# ESP32_S2.net
KiCad netlist of a schematic drawn in Altium Designer
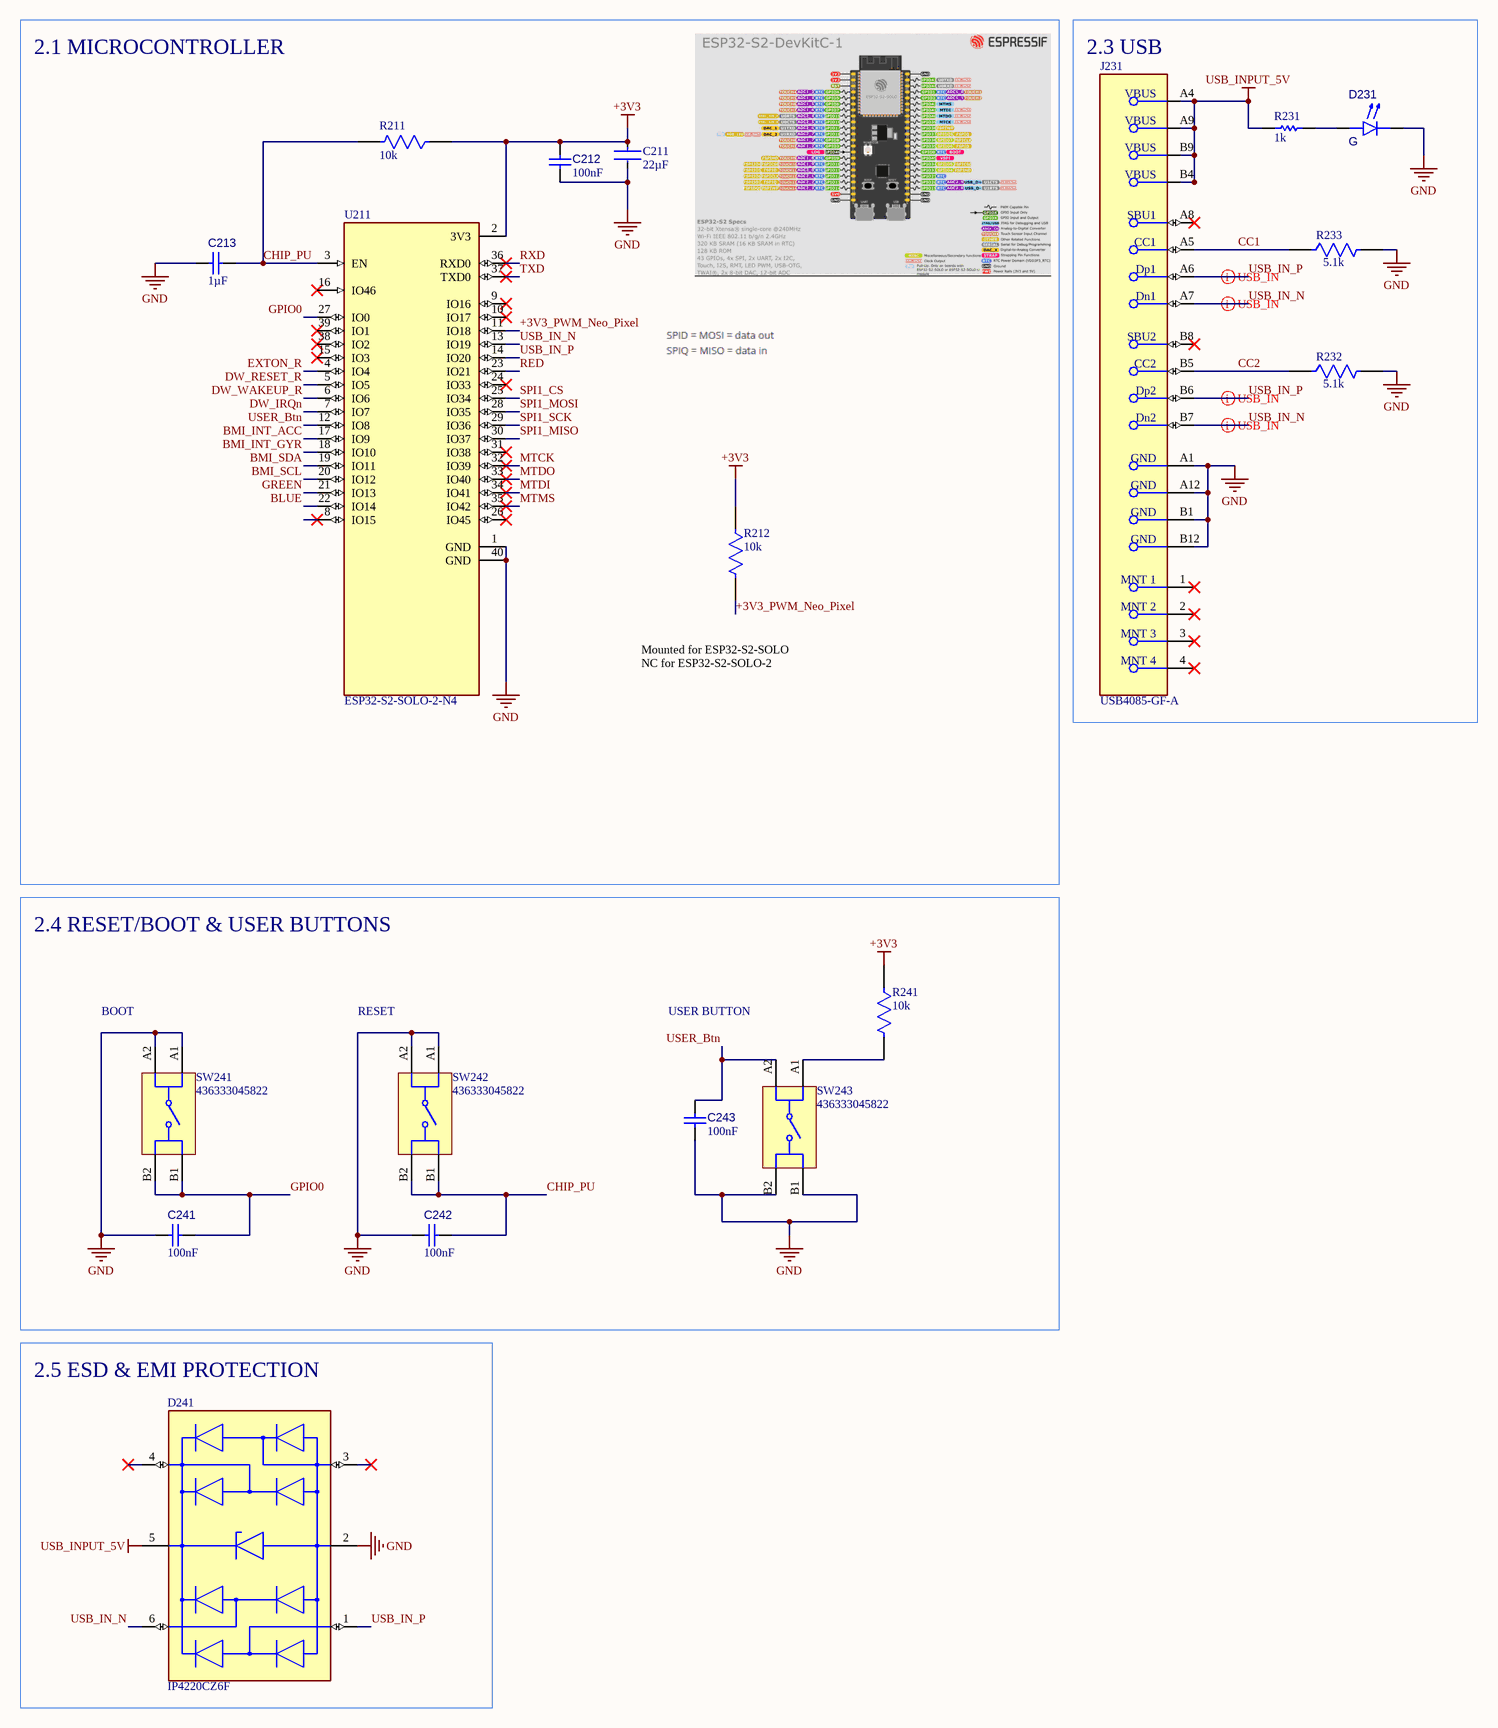
[diagram p0: ESP32_S2.SchDoc]

(export (version "E")
  (design (tool "Eeschema 10.0.6"))
  (components
    (comp (ref "C211")
      (value "22µF")
      (footprint "FP-GRM21B-0_2-e0_2_0_7-MFG")
      (fields (field (name "Comment") "GRM21BZ71A226ME15L"))
      (libsource (lib "University of British Columbia") (part "b4654b650e69147ec39a6b967a45e02"))
    )
    (comp (ref "C212")
      (value "100nF")
      (footprint "CAPC0402(1005)60_L")
      (description "Chip Capacitor, 100nF +/-20%, 10V, 0402, Thickness 0.6 mm")
      (fields (field (name "TOLERANCE") "20%") (field (name "Comment") "Capacitor 100nF +/-20% 10V 0402"))
      (libsource (lib "University of British Columbia") (part "CAP-NP-2"))
    )
    (comp (ref "C213")
      (value "1µF")
      (footprint "CAPC0402(1005)60_L")
      (description "Chip Capacitor, 1µF +/-20%, 10V, 0402, Thickness 0.6 mm")
      (fields (field (name "TOLERANCE") "10%") (field (name "Comment") "Capacitor 1µF +/-20% 10V 0402"))
      (libsource (lib "University of British Columbia") (part "CAP-NP-2"))
    )
    (comp (ref "C241")
      (value "100nF")
      (footprint "CAPC1005X56X25LL10T15")
      (description "Chip Capacitor, 0.1 uF, +/- 5%, 16 V, 0402 (1005 Metric)")
      (fields (field (name "TOLERANCE") "5%") (field (name "Comment") "Capacitor 0.1 uF +/- 5% 16 V 0402"))
      (libsource (lib "University of British Columbia") (part "CAP-NP-2"))
    )
    (comp (ref "C242")
      (value "100nF")
      (footprint "CAPC1005X56X25LL10T15")
      (description "Chip Capacitor, 0.1 uF, +/- 5%, 16 V, 0402 (1005 Metric)")
      (fields (field (name "TOLERANCE") "5%") (field (name "Comment") "Capacitor 0.1 uF +/- 5% 16 V 0402"))
      (libsource (lib "University of British Columbia") (part "CAP-NP-2"))
    )
    (comp (ref "C243")
      (value "100nF")
      (footprint "CAPC1005X56X25LL10T15")
      (description "Chip Capacitor, 0.1 uF, +/- 5%, 16 V, 0402 (1005 Metric)")
      (fields (field (name "TOLERANCE") "5%") (field (name "Comment") "Capacitor 0.1 uF +/- 5% 16 V 0402"))
      (libsource (lib "University of British Columbia") (part "CAP-NP-2"))
    )
    (comp (ref "D231")
      (value "G")
      (footprint "WL-SMCW_0603_150060xx75000")
      (description "Single Color LED, Green, Water Clear, 1.1mm")
      (libsource (lib "University of British Columbia") (part "DIODE-LED-2"))
    )
    (comp (ref "D241")
      (value "IP4220CZ6F")
      (footprint "FP-SOT457-IPC_C")
      (description "Trans Voltage Suppressor Diode, Unidirectional, 1 Element, Silicon")
      (libsource (lib "University of British Columbia") (part "c90fc1b224fbf844a1d07a8dc5e9dc1"))
    )
    (comp (ref "J231")
      (value "USB4085-GF-A")
      (footprint "FP-USB4085-GF-A-MFG")
      (description "USB Connector, 16 Contact(s), Female, Right Angle, Solder Terminal, Receptacle")
      (libsource (lib "University of British Columbia") (part "10fa745527c8b974685cbca3c197132"))
    )
    (comp (ref "R211")
      (value "10k")
      (footprint "FP-RC0402-0_4-MFG")
      (fields
        (field (name "TOLERANCE") "5%")
        (field (name "POWER") "62.5mW")
        (field (name "Comment") "RC0402JR-0710KL")
      )
      (libsource (lib "University of British Columbia") (part "1029c3af85768c4190bb7ad29bc67b5"))
    )
    (comp (ref "R212")
      (value "10k")
      (footprint "FP-RC0402-0_4-MFG")
      (fields
        (field (name "TOLERANCE") "5%")
        (field (name "POWER") "62.5mW")
        (field (name "Comment") "RC0402JR-0710KL")
      )
      (libsource (lib "University of British Columbia") (part "1029c3af85768c4190bb7ad29bc67b5"))
    )
    (comp (ref "R231")
      (value "1k")
      (footprint "RESC2013X60X35ML10T20")
      (fields
        (field (name "TOLERANCE") "1%")
        (field (name "POWER") "125mW")
        (field (name "Comment") "RC0805FR-071KL")
      )
      (libsource (lib "University of British Columbia") (part "RES-2"))
    )
    (comp (ref "R232")
      (value "5.1k")
      (footprint "FP-RT0402-IPC_B")
      (description "Fixed Resistor, Thin Film, 0.0625W, 5100ohm, 50V, 0.5% +/-Tol, 50ppm/Cel, Surface Mount, 0402")
      (fields (field (name "POWER") "62.5mW") (field (name "TOLERANCE") "0.5%"))
      (libsource (lib "University of British Columbia") (part "1029c3af85768c4190bb7ad29bc67b5"))
    )
    (comp (ref "R233")
      (value "5.1k")
      (footprint "FP-RT0402-IPC_B")
      (description "Fixed Resistor, Thin Film, 0.0625W, 5100ohm, 50V, 0.5% +/-Tol, 50ppm/Cel, Surface Mount, 0402")
      (fields (field (name "POWER") "62.5mW") (field (name "TOLERANCE") "0.5%"))
      (libsource (lib "University of British Columbia") (part "1029c3af85768c4190bb7ad29bc67b5"))
    )
    (comp (ref "R241")
      (value "10k")
      (footprint "FP-RC0402-0_4-MFG")
      (fields
        (field (name "TOLERANCE") "5%")
        (field (name "POWER") "62.5mW")
        (field (name "Comment") "RC0402JR-0710KL")
      )
      (libsource (lib "University of British Columbia") (part "1029c3af85768c4190bb7ad29bc67b5"))
    )
    (comp (ref "SW241")
      (value "436333045822")
      (footprint "436333045822")
      (libsource (lib "University of British Columbia") (part "SPST-NO_4P"))
    )
    (comp (ref "SW242")
      (value "436333045822")
      (footprint "436333045822")
      (libsource (lib "University of British Columbia") (part "SPST-NO_4P"))
    )
    (comp (ref "SW243")
      (value "436333045822")
      (footprint "436333045822")
      (libsource (lib "University of British Columbia") (part "SPST-NO_4P"))
    )
    (comp (ref "U211")
      (value "ESP32-S2-SOLO-2-N4")
      (footprint "XCVR_ESP32-S2-SOLO-N4")
      (description "SMD Module, ESP32-S2, 4 mb Spi F")
      (fields (field (name "MF") "Espressif Systems") (field (name "MP") "ESP32-S2-SOLO-N4"))
      (libsource (lib "University of British Columbia") (part "ESP32-S2-SOLO-N4"))
    )
  )
  (nets
    (net (code "1") (name "+3V3") (class "Default")
      (node (ref "C211") (pin "1") (pinfunction "1_1") (pintype "passive"))
      (node (ref "C212") (pin "2") (pinfunction "2_2") (pintype "passive"))
      (node (ref "R211") (pin "1") (pinfunction "1_1") (pintype "passive"))
      (node (ref "R212") (pin "1") (pinfunction "1_1") (pintype "passive"))
      (node (ref "R241") (pin "1") (pinfunction "1_1") (pintype "passive"))
      (node (ref "U211") (pin "2") (pinfunction "3V3_2") (pintype "power_in"))
    )
    (net (code "2") (name "/+3V3_PWM_Neo_Pixel") (class "Default")
      (node (ref "R212") (pin "2") (pinfunction "2_2") (pintype "passive"))
      (node (ref "U211") (pin "11") (pinfunction "IO18_11") (pintype "bidirectional"))
    )
    (net (code "3") (name "/BLUE") (class "Default")
      (node (ref "U211") (pin "22") (pinfunction "IO14_22") (pintype "bidirectional"))
    )
    (net (code "4") (name "/BMI_INT_ACC") (class "Default")
      (node (ref "U211") (pin "17") (pinfunction "IO9_17") (pintype "bidirectional"))
    )
    (net (code "5") (name "/BMI_INT_GYR") (class "Default")
      (node (ref "U211") (pin "18") (pinfunction "IO10_18") (pintype "bidirectional"))
    )
    (net (code "6") (name "/BMI_SCL") (class "Default")
      (node (ref "U211") (pin "20") (pinfunction "IO12_20") (pintype "bidirectional"))
    )
    (net (code "7") (name "/BMI_SDA") (class "Default")
      (node (ref "U211") (pin "19") (pinfunction "IO11_19") (pintype "bidirectional"))
    )
    (net (code "8") (name "/CC1") (class "Default")
      (node (ref "J231") (pin "A5") (pinfunction "CC1_A5") (pintype "bidirectional"))
      (node (ref "R233") (pin "1") (pinfunction "1_1") (pintype "passive"))
    )
    (net (code "9") (name "/CC2") (class "Default")
      (node (ref "J231") (pin "B5") (pinfunction "CC2_B5") (pintype "bidirectional"))
      (node (ref "R232") (pin "1") (pinfunction "1_1") (pintype "passive"))
    )
    (net (code "10") (name "/CHIP_PU") (class "Default")
      (node (ref "C213") (pin "1") (pinfunction "1_1") (pintype "passive"))
      (node (ref "C242") (pin "2") (pinfunction "2_2") (pintype "passive"))
      (node (ref "R211") (pin "2") (pinfunction "2_2") (pintype "passive"))
      (node (ref "SW242") (pin "B1") (pinfunction "B1_B1") (pintype "passive"))
      (node (ref "SW242") (pin "B2") (pinfunction "B2_B2") (pintype "passive"))
      (node (ref "U211") (pin "3") (pinfunction "EN_3") (pintype "input"))
    )
    (net (code "11") (name "/DW_IRQn") (class "Default")
      (node (ref "U211") (pin "7") (pinfunction "IO7_7") (pintype "bidirectional"))
    )
    (net (code "12") (name "/DW_RESET_R") (class "Default")
      (node (ref "U211") (pin "5") (pinfunction "IO5_5") (pintype "bidirectional"))
    )
    (net (code "13") (name "/DW_WAKEUP_R") (class "Default")
      (node (ref "U211") (pin "6") (pinfunction "IO6_6") (pintype "bidirectional"))
    )
    (net (code "14") (name "/EXTON_R") (class "Default")
      (node (ref "U211") (pin "4") (pinfunction "IO4_4") (pintype "bidirectional"))
    )
    (net (code "15") (name "/GPIO0") (class "Default")
      (node (ref "C241") (pin "2") (pinfunction "2_2") (pintype "passive"))
      (node (ref "SW241") (pin "B1") (pinfunction "B1_B1") (pintype "passive"))
      (node (ref "SW241") (pin "B2") (pinfunction "B2_B2") (pintype "passive"))
      (node (ref "U211") (pin "27") (pinfunction "IO0_27") (pintype "bidirectional"))
    )
    (net (code "16") (name "/GREEN") (class "Default")
      (node (ref "U211") (pin "21") (pinfunction "IO13_21") (pintype "bidirectional"))
    )
    (net (code "17") (name "/MTCK") (class "Default")
      (node (ref "U211") (pin "32") (pinfunction "IO39_32") (pintype "bidirectional+no_connect"))
    )
    (net (code "18") (name "/MTDI") (class "Default")
      (node (ref "U211") (pin "34") (pinfunction "IO41_34") (pintype "bidirectional+no_connect"))
    )
    (net (code "19") (name "/MTDO") (class "Default")
      (node (ref "U211") (pin "33") (pinfunction "IO40_33") (pintype "bidirectional+no_connect"))
    )
    (net (code "20") (name "/MTMS") (class "Default")
      (node (ref "U211") (pin "35") (pinfunction "IO42_35") (pintype "bidirectional+no_connect"))
    )
    (net (code "21") (name "/RED") (class "Default")
      (node (ref "U211") (pin "23") (pinfunction "IO21_23") (pintype "bidirectional"))
    )
    (net (code "22") (name "/RXD") (class "Default")
      (node (ref "U211") (pin "36") (pinfunction "RXD0_36") (pintype "bidirectional+no_connect"))
    )
    (net (code "23") (name "/SPI1_CS") (class "Default")
      (node (ref "U211") (pin "25") (pinfunction "IO34_25") (pintype "bidirectional"))
    )
    (net (code "24") (name "/SPI1_MISO") (class "Default")
      (node (ref "U211") (pin "30") (pinfunction "IO37_30") (pintype "bidirectional"))
    )
    (net (code "25") (name "/SPI1_MOSI") (class "Default")
      (node (ref "U211") (pin "28") (pinfunction "IO35_28") (pintype "bidirectional"))
    )
    (net (code "26") (name "/SPI1_SCK") (class "Default")
      (node (ref "U211") (pin "29") (pinfunction "IO36_29") (pintype "bidirectional"))
    )
    (net (code "27") (name "/TXD") (class "Default")
      (node (ref "U211") (pin "37") (pinfunction "TXD0_37") (pintype "bidirectional+no_connect"))
    )
    (net (code "28") (name "/USB_IN_N") (class "Default")
      (node (ref "D241") (pin "6") (pinfunction "I/O4_6") (pintype "bidirectional"))
      (node (ref "J231") (pin "A7") (pinfunction "Dn1_A7") (pintype "bidirectional"))
      (node (ref "J231") (pin "B7") (pinfunction "Dn2_B7") (pintype "bidirectional"))
      (node (ref "U211") (pin "13") (pinfunction "IO19_13") (pintype "bidirectional"))
    )
    (net (code "29") (name "/USB_IN_P") (class "Default")
      (node (ref "D241") (pin "1") (pinfunction "I/O1_1") (pintype "bidirectional"))
      (node (ref "J231") (pin "A6") (pinfunction "Dp1_A6") (pintype "bidirectional"))
      (node (ref "J231") (pin "B6") (pinfunction "Dp2_B6") (pintype "bidirectional"))
      (node (ref "U211") (pin "14") (pinfunction "IO20_14") (pintype "bidirectional"))
    )
    (net (code "30") (name "/USER_Btn") (class "Default")
      (node (ref "C243") (pin "2") (pinfunction "2_2") (pintype "passive"))
      (node (ref "SW243") (pin "A2") (pinfunction "A2_A2") (pintype "passive"))
      (node (ref "U211") (pin "12") (pinfunction "IO8_12") (pintype "bidirectional"))
    )
    (net (code "31") (name "GND") (class "Default")
      (node (ref "C211") (pin "2") (pinfunction "2_2") (pintype "passive"))
      (node (ref "C212") (pin "1") (pinfunction "1_1") (pintype "passive"))
      (node (ref "C213") (pin "2") (pinfunction "2_2") (pintype "passive"))
      (node (ref "C241") (pin "1") (pinfunction "1_1") (pintype "passive"))
      (node (ref "C242") (pin "1") (pinfunction "1_1") (pintype "passive"))
      (node (ref "C243") (pin "1") (pinfunction "1_1") (pintype "passive"))
      (node (ref "D231") (pin "1") (pinfunction "K_1") (pintype "passive"))
      (node (ref "D241") (pin "2") (pinfunction "GND_2") (pintype "power_in"))
      (node (ref "J231") (pin "A1") (pinfunction "GND_A1") (pintype "power_in"))
      (node (ref "J231") (pin "A12") (pinfunction "GND_A12") (pintype "power_in"))
      (node (ref "J231") (pin "B1") (pinfunction "GND_B1") (pintype "power_in"))
      (node (ref "J231") (pin "B12") (pinfunction "GND_B12") (pintype "power_in"))
      (node (ref "R232") (pin "2") (pinfunction "2_2") (pintype "passive"))
      (node (ref "R233") (pin "2") (pinfunction "2_2") (pintype "passive"))
      (node (ref "SW241") (pin "A1") (pinfunction "A1_A1") (pintype "passive"))
      (node (ref "SW241") (pin "A2") (pinfunction "A2_A2") (pintype "passive"))
      (node (ref "SW242") (pin "A1") (pinfunction "A1_A1") (pintype "passive"))
      (node (ref "SW242") (pin "A2") (pinfunction "A2_A2") (pintype "passive"))
      (node (ref "SW243") (pin "B1") (pinfunction "B1_B1") (pintype "passive"))
      (node (ref "SW243") (pin "B2") (pinfunction "B2_B2") (pintype "passive"))
      (node (ref "U211") (pin "1") (pinfunction "GND_1") (pintype "power_in"))
      (node (ref "U211") (pin "40") (pinfunction "GND_40") (pintype "power_in"))
    )
    (net (code "32") (name "Net-(D231-A)") (class "Default")
      (node (ref "D231") (pin "2") (pinfunction "A_2") (pintype "passive"))
      (node (ref "R231") (pin "2") (pinfunction "2_2") (pintype "passive"))
    )
    (net (code "33") (name "Net-(R241-Pad2)") (class "Default")
      (node (ref "R241") (pin "2") (pinfunction "2_2") (pintype "passive"))
      (node (ref "SW243") (pin "A1") (pinfunction "A1_A1") (pintype "passive"))
    )
    (net (code "34") (name "USB_INPUT_5V") (class "Default")
      (node (ref "D241") (pin "5") (pinfunction "VP_5") (pintype "power_in"))
      (node (ref "J231") (pin "A4") (pinfunction "VBUS_A4") (pintype "power_in"))
      (node (ref "J231") (pin "A9") (pinfunction "VBUS_A9") (pintype "power_in"))
      (node (ref "J231") (pin "B4") (pinfunction "VBUS_B4") (pintype "power_in"))
      (node (ref "J231") (pin "B9") (pinfunction "VBUS_B9") (pintype "power_in"))
      (node (ref "R231") (pin "1") (pinfunction "1_1") (pintype "passive"))
    )
    (net (code "35") (name "unconnected-(D241-I{slash}O2-Pad3)") (class "Default")
      (node (ref "D241") (pin "3") (pinfunction "I/O2_3") (pintype "bidirectional+no_connect"))
    )
    (net (code "36") (name "unconnected-(D241-I{slash}O3-Pad4)") (class "Default")
      (node (ref "D241") (pin "4") (pinfunction "I/O3_4") (pintype "bidirectional+no_connect"))
    )
    (net (code "37") (name "unconnected-(J231-MNT_1-Pad1)") (class "Default")
      (node (ref "J231") (pin "1") (pinfunction "MNT_1_1") (pintype "passive+no_connect"))
    )
    (net (code "38") (name "unconnected-(J231-MNT_2-Pad2)") (class "Default")
      (node (ref "J231") (pin "2") (pinfunction "MNT_2_2") (pintype "passive+no_connect"))
    )
    (net (code "39") (name "unconnected-(J231-MNT_3-Pad3)") (class "Default")
      (node (ref "J231") (pin "3") (pinfunction "MNT_3_3") (pintype "passive+no_connect"))
    )
    (net (code "40") (name "unconnected-(J231-MNT_4-Pad4)") (class "Default")
      (node (ref "J231") (pin "4") (pinfunction "MNT_4_4") (pintype "passive+no_connect"))
    )
    (net (code "41") (name "unconnected-(J231-SBU1-PadA8)") (class "Default")
      (node (ref "J231") (pin "A8") (pinfunction "SBU1_A8") (pintype "bidirectional+no_connect"))
    )
    (net (code "42") (name "unconnected-(J231-SBU2-PadB8)") (class "Default")
      (node (ref "J231") (pin "B8") (pinfunction "SBU2_B8") (pintype "bidirectional+no_connect"))
    )
    (net (code "43") (name "unconnected-(U211-IO1-Pad39)") (class "Default")
      (node (ref "U211") (pin "39") (pinfunction "IO1_39") (pintype "bidirectional+no_connect"))
    )
    (net (code "44") (name "unconnected-(U211-IO2-Pad38)") (class "Default")
      (node (ref "U211") (pin "38") (pinfunction "IO2_38") (pintype "bidirectional+no_connect"))
    )
    (net (code "45") (name "unconnected-(U211-IO3-Pad15)") (class "Default")
      (node (ref "U211") (pin "15") (pinfunction "IO3_15") (pintype "bidirectional+no_connect"))
    )
    (net (code "46") (name "unconnected-(U211-IO15-Pad8)") (class "Default")
      (node (ref "U211") (pin "8") (pinfunction "IO15_8") (pintype "bidirectional+no_connect"))
    )
    (net (code "47") (name "unconnected-(U211-IO16-Pad9)") (class "Default")
      (node (ref "U211") (pin "9") (pinfunction "IO16_9") (pintype "bidirectional+no_connect"))
    )
    (net (code "48") (name "unconnected-(U211-IO17-Pad10)") (class "Default")
      (node (ref "U211") (pin "10") (pinfunction "IO17_10") (pintype "bidirectional+no_connect"))
    )
    (net (code "49") (name "unconnected-(U211-IO33-Pad24)") (class "Default")
      (node (ref "U211") (pin "24") (pinfunction "IO33_24") (pintype "bidirectional+no_connect"))
    )
    (net (code "50") (name "unconnected-(U211-IO38-Pad31)") (class "Default")
      (node (ref "U211") (pin "31") (pinfunction "IO38_31") (pintype "bidirectional+no_connect"))
    )
    (net (code "51") (name "unconnected-(U211-IO45-Pad26)") (class "Default")
      (node (ref "U211") (pin "26") (pinfunction "IO45_26") (pintype "bidirectional+no_connect"))
    )
    (net (code "52") (name "unconnected-(U211-IO46-Pad16)") (class "Default")
      (node (ref "U211") (pin "16") (pinfunction "IO46_16") (pintype "input+no_connect"))
    )
  )
)
